# GPIO.net
KiCad netlist of a schematic drawn in Altium Designer
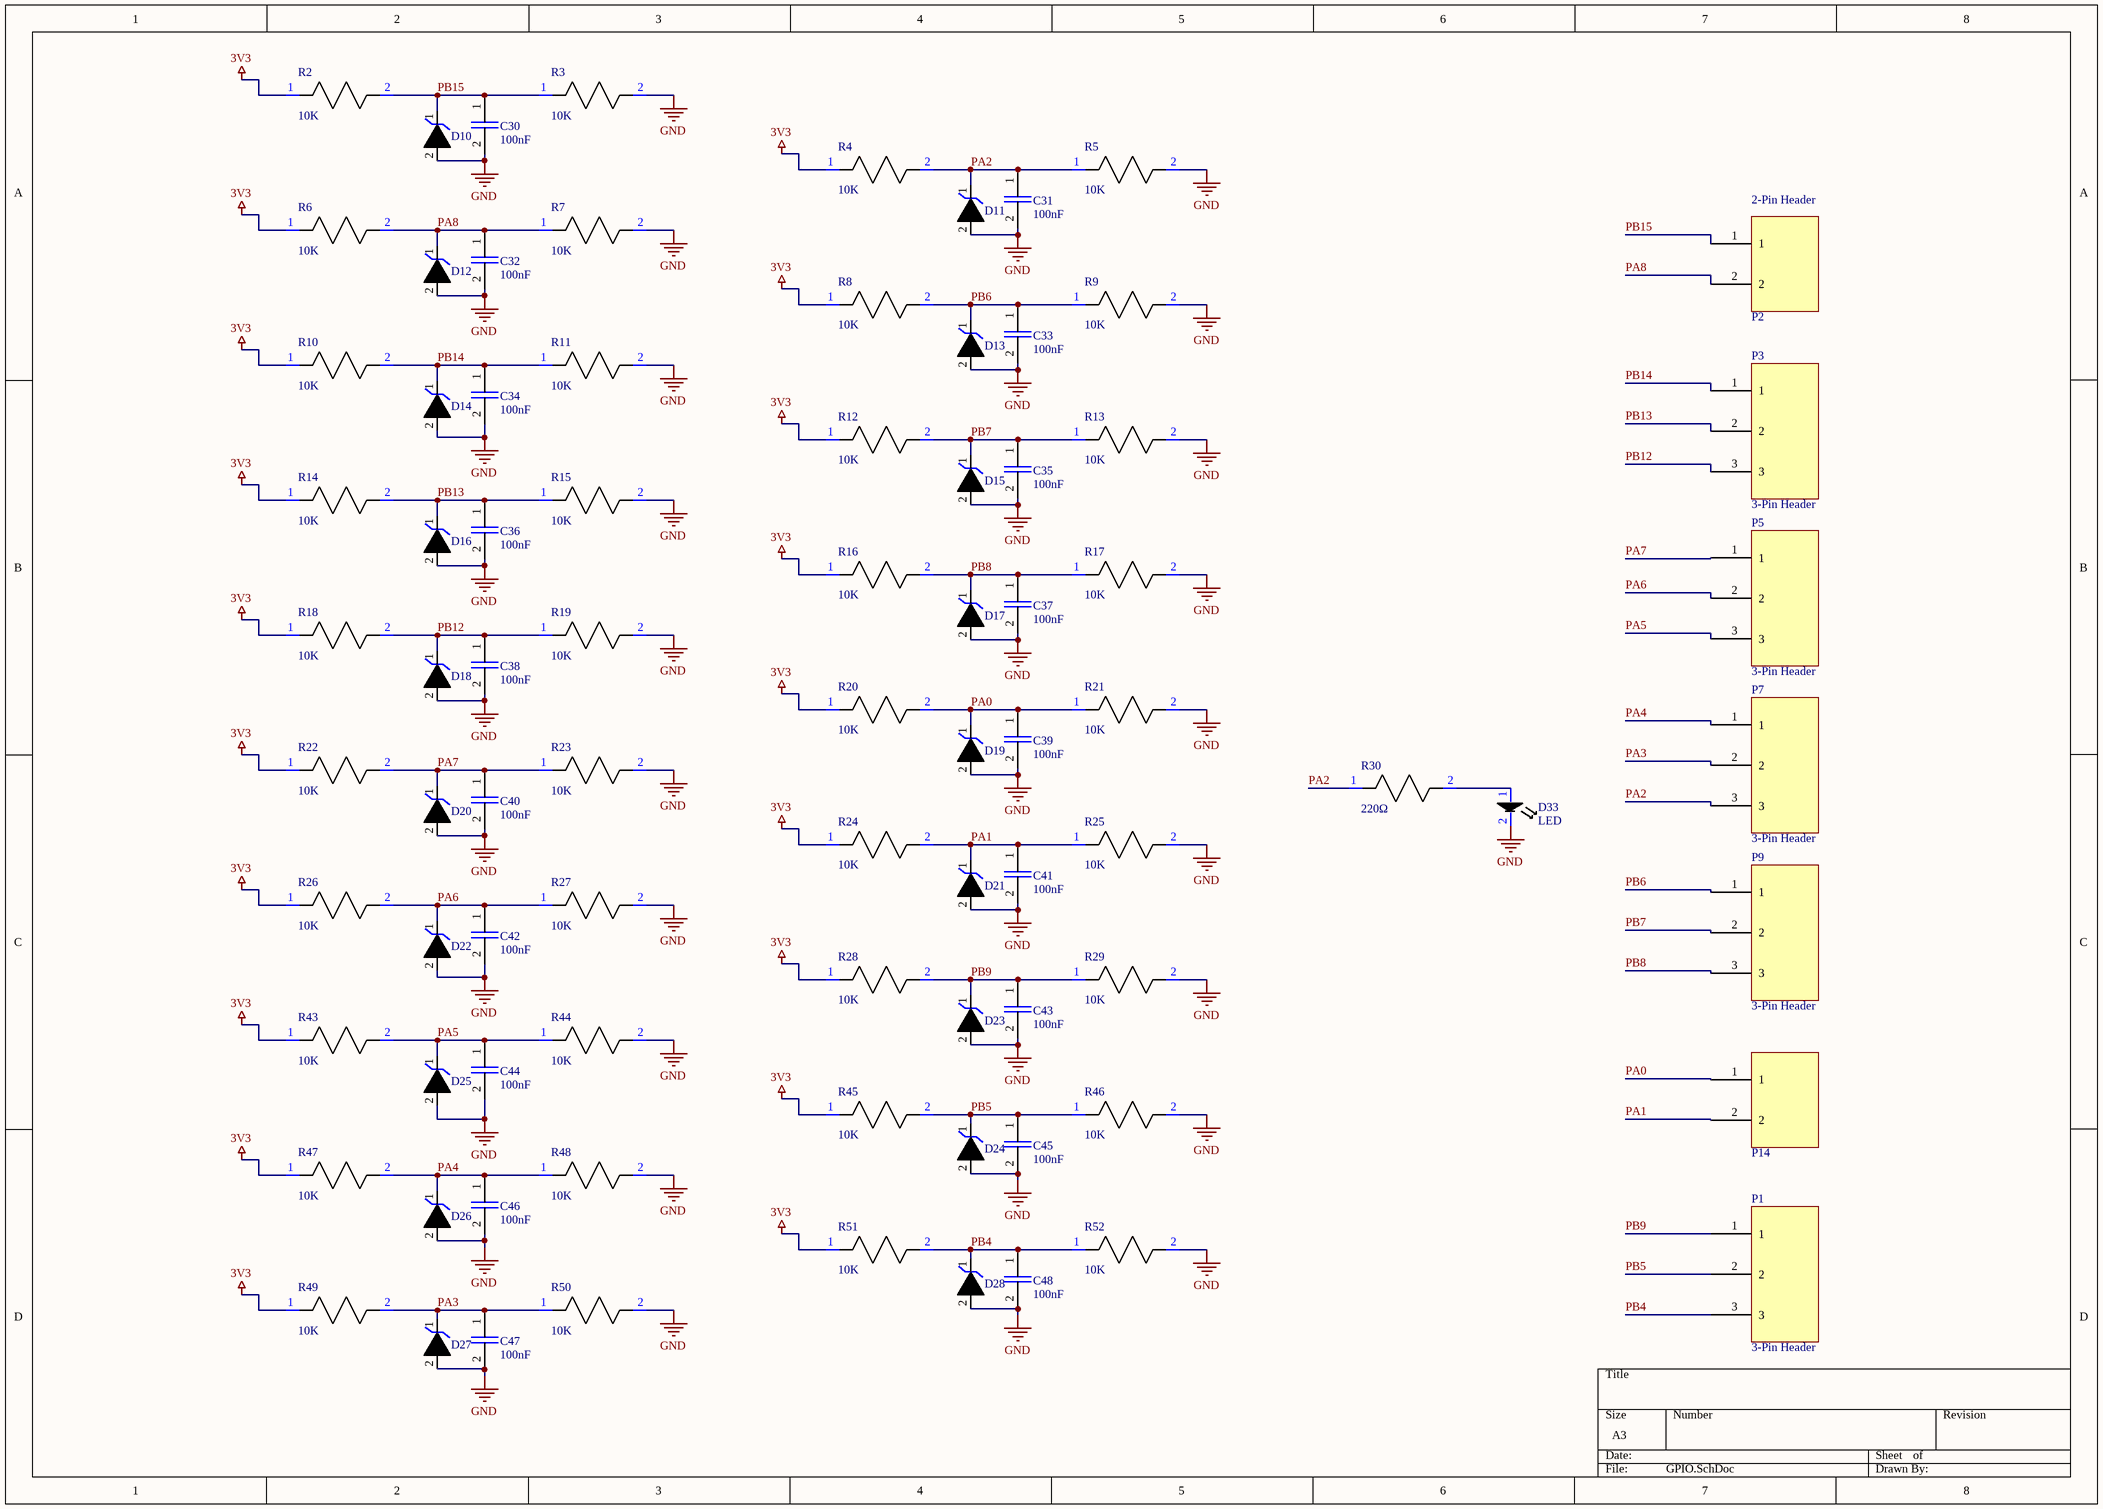
[diagram p0: GPIO.SchDoc]

(export (version "E")
  (design (tool "Eeschema 10.0.6"))
  (components
    (comp (ref "C30")
      (value "100nF")
      (footprint "0603 Cap")
      (description "SMD 0603 (ceramic) capacitor")
      (fields
        (field (name "MANUFACTURER") "Murata")
        (field (name "MANUFACTURER PART NUMBER") "GRM21BR71C225KA12L")
      )
      (libsource (lib "Lib") (part "0603 Cap"))
    )
    (comp (ref "C31")
      (value "100nF")
      (footprint "0603 Cap")
      (description "SMD 0603 (ceramic) capacitor")
      (fields
        (field (name "MANUFACTURER") "Murata")
        (field (name "MANUFACTURER PART NUMBER") "GRM21BR71C225KA12L")
      )
      (libsource (lib "Lib") (part "0603 Cap"))
    )
    (comp (ref "C32")
      (value "100nF")
      (footprint "0603 Cap")
      (description "SMD 0603 (ceramic) capacitor")
      (fields
        (field (name "MANUFACTURER") "Murata")
        (field (name "MANUFACTURER PART NUMBER") "GRM21BR71C225KA12L")
      )
      (libsource (lib "Lib") (part "0603 Cap"))
    )
    (comp (ref "C33")
      (value "100nF")
      (footprint "0603 Cap")
      (description "SMD 0603 (ceramic) capacitor")
      (fields
        (field (name "MANUFACTURER") "Murata")
        (field (name "MANUFACTURER PART NUMBER") "GRM21BR71C225KA12L")
      )
      (libsource (lib "Lib") (part "0603 Cap"))
    )
    (comp (ref "C34")
      (value "100nF")
      (footprint "0603 Cap")
      (description "SMD 0603 (ceramic) capacitor")
      (fields
        (field (name "MANUFACTURER") "Murata")
        (field (name "MANUFACTURER PART NUMBER") "GRM21BR71C225KA12L")
      )
      (libsource (lib "Lib") (part "0603 Cap"))
    )
    (comp (ref "C35")
      (value "100nF")
      (footprint "0603 Cap")
      (description "SMD 0603 (ceramic) capacitor")
      (fields
        (field (name "MANUFACTURER") "Murata")
        (field (name "MANUFACTURER PART NUMBER") "GRM21BR71C225KA12L")
      )
      (libsource (lib "Lib") (part "0603 Cap"))
    )
    (comp (ref "C36")
      (value "100nF")
      (footprint "0603 Cap")
      (description "SMD 0603 (ceramic) capacitor")
      (fields
        (field (name "MANUFACTURER") "Murata")
        (field (name "MANUFACTURER PART NUMBER") "GRM21BR71C225KA12L")
      )
      (libsource (lib "Lib") (part "0603 Cap"))
    )
    (comp (ref "C37")
      (value "100nF")
      (footprint "0603 Cap")
      (description "SMD 0603 (ceramic) capacitor")
      (fields
        (field (name "MANUFACTURER") "Murata")
        (field (name "MANUFACTURER PART NUMBER") "GRM21BR71C225KA12L")
      )
      (libsource (lib "Lib") (part "0603 Cap"))
    )
    (comp (ref "C38")
      (value "100nF")
      (footprint "0603 Cap")
      (description "SMD 0603 (ceramic) capacitor")
      (fields
        (field (name "MANUFACTURER") "Murata")
        (field (name "MANUFACTURER PART NUMBER") "GRM21BR71C225KA12L")
      )
      (libsource (lib "Lib") (part "0603 Cap"))
    )
    (comp (ref "C39")
      (value "100nF")
      (footprint "0603 Cap")
      (description "SMD 0603 (ceramic) capacitor")
      (fields
        (field (name "MANUFACTURER") "Murata")
        (field (name "MANUFACTURER PART NUMBER") "GRM21BR71C225KA12L")
      )
      (libsource (lib "Lib") (part "0603 Cap"))
    )
    (comp (ref "C40")
      (value "100nF")
      (footprint "0603 Cap")
      (description "SMD 0603 (ceramic) capacitor")
      (fields
        (field (name "MANUFACTURER") "Murata")
        (field (name "MANUFACTURER PART NUMBER") "GRM21BR71C225KA12L")
      )
      (libsource (lib "Lib") (part "0603 Cap"))
    )
    (comp (ref "C41")
      (value "100nF")
      (footprint "0603 Cap")
      (description "SMD 0603 (ceramic) capacitor")
      (fields
        (field (name "MANUFACTURER") "Murata")
        (field (name "MANUFACTURER PART NUMBER") "GRM21BR71C225KA12L")
      )
      (libsource (lib "Lib") (part "0603 Cap"))
    )
    (comp (ref "C42")
      (value "100nF")
      (footprint "0603 Cap")
      (description "SMD 0603 (ceramic) capacitor")
      (fields
        (field (name "MANUFACTURER") "Murata")
        (field (name "MANUFACTURER PART NUMBER") "GRM21BR71C225KA12L")
      )
      (libsource (lib "Lib") (part "0603 Cap"))
    )
    (comp (ref "C43")
      (value "100nF")
      (footprint "0603 Cap")
      (description "SMD 0603 (ceramic) capacitor")
      (fields
        (field (name "MANUFACTURER") "Murata")
        (field (name "MANUFACTURER PART NUMBER") "GRM21BR71C225KA12L")
      )
      (libsource (lib "Lib") (part "0603 Cap"))
    )
    (comp (ref "C44")
      (value "100nF")
      (footprint "0603 Cap")
      (description "SMD 0603 (ceramic) capacitor")
      (fields
        (field (name "MANUFACTURER") "Murata")
        (field (name "MANUFACTURER PART NUMBER") "GRM21BR71C225KA12L")
      )
      (libsource (lib "Lib") (part "0603 Cap"))
    )
    (comp (ref "C45")
      (value "100nF")
      (footprint "0603 Cap")
      (description "SMD 0603 (ceramic) capacitor")
      (fields
        (field (name "MANUFACTURER") "Murata")
        (field (name "MANUFACTURER PART NUMBER") "GRM21BR71C225KA12L")
      )
      (libsource (lib "Lib") (part "0603 Cap"))
    )
    (comp (ref "C46")
      (value "100nF")
      (footprint "0603 Cap")
      (description "SMD 0603 (ceramic) capacitor")
      (fields
        (field (name "MANUFACTURER") "Murata")
        (field (name "MANUFACTURER PART NUMBER") "GRM21BR71C225KA12L")
      )
      (libsource (lib "Lib") (part "0603 Cap"))
    )
    (comp (ref "C47")
      (value "100nF")
      (footprint "0603 Cap")
      (description "SMD 0603 (ceramic) capacitor")
      (fields
        (field (name "MANUFACTURER") "Murata")
        (field (name "MANUFACTURER PART NUMBER") "GRM21BR71C225KA12L")
      )
      (libsource (lib "Lib") (part "0603 Cap"))
    )
    (comp (ref "C48")
      (value "100nF")
      (footprint "0603 Cap")
      (description "SMD 0603 (ceramic) capacitor")
      (fields
        (field (name "MANUFACTURER") "Murata")
        (field (name "MANUFACTURER PART NUMBER") "GRM21BR71C225KA12L")
      )
      (libsource (lib "Lib") (part "0603 Cap"))
    )
    (comp (ref "D10")
      (value "TVS")
      (footprint "TVS DIODE")
      (description "Schematic for TVS diode")
      (libsource (lib "Lib") (part "TVS Diode"))
    )
    (comp (ref "D11")
      (value "TVS")
      (footprint "TVS DIODE")
      (description "Schematic for TVS diode")
      (libsource (lib "Lib") (part "TVS Diode"))
    )
    (comp (ref "D12")
      (value "TVS")
      (footprint "TVS DIODE")
      (description "Schematic for TVS diode")
      (libsource (lib "Lib") (part "TVS Diode"))
    )
    (comp (ref "D13")
      (value "TVS")
      (footprint "TVS DIODE")
      (description "Schematic for TVS diode")
      (libsource (lib "Lib") (part "TVS Diode"))
    )
    (comp (ref "D14")
      (value "TVS")
      (footprint "TVS DIODE")
      (description "Schematic for TVS diode")
      (libsource (lib "Lib") (part "TVS Diode"))
    )
    (comp (ref "D15")
      (value "TVS")
      (footprint "TVS DIODE")
      (description "Schematic for TVS diode")
      (libsource (lib "Lib") (part "TVS Diode"))
    )
    (comp (ref "D16")
      (value "TVS")
      (footprint "TVS DIODE")
      (description "Schematic for TVS diode")
      (libsource (lib "Lib") (part "TVS Diode"))
    )
    (comp (ref "D17")
      (value "TVS")
      (footprint "TVS DIODE")
      (description "Schematic for TVS diode")
      (libsource (lib "Lib") (part "TVS Diode"))
    )
    (comp (ref "D18")
      (value "TVS")
      (footprint "TVS DIODE")
      (description "Schematic for TVS diode")
      (libsource (lib "Lib") (part "TVS Diode"))
    )
    (comp (ref "D19")
      (value "TVS")
      (footprint "TVS DIODE")
      (description "Schematic for TVS diode")
      (libsource (lib "Lib") (part "TVS Diode"))
    )
    (comp (ref "D20")
      (value "TVS")
      (footprint "TVS DIODE")
      (description "Schematic for TVS diode")
      (libsource (lib "Lib") (part "TVS Diode"))
    )
    (comp (ref "D21")
      (value "TVS")
      (footprint "TVS DIODE")
      (description "Schematic for TVS diode")
      (libsource (lib "Lib") (part "TVS Diode"))
    )
    (comp (ref "D22")
      (value "TVS")
      (footprint "TVS DIODE")
      (description "Schematic for TVS diode")
      (libsource (lib "Lib") (part "TVS Diode"))
    )
    (comp (ref "D23")
      (value "TVS")
      (footprint "TVS DIODE")
      (description "Schematic for TVS diode")
      (libsource (lib "Lib") (part "TVS Diode"))
    )
    (comp (ref "D24")
      (value "TVS")
      (footprint "TVS DIODE")
      (description "Schematic for TVS diode")
      (libsource (lib "Lib") (part "TVS Diode"))
    )
    (comp (ref "D25")
      (value "TVS")
      (footprint "TVS DIODE")
      (description "Schematic for TVS diode")
      (libsource (lib "Lib") (part "TVS Diode"))
    )
    (comp (ref "D26")
      (value "TVS")
      (footprint "TVS DIODE")
      (description "Schematic for TVS diode")
      (libsource (lib "Lib") (part "TVS Diode"))
    )
    (comp (ref "D27")
      (value "TVS")
      (footprint "TVS DIODE")
      (description "Schematic for TVS diode")
      (libsource (lib "Lib") (part "TVS Diode"))
    )
    (comp (ref "D28")
      (value "TVS")
      (footprint "TVS DIODE")
      (description "Schematic for TVS diode")
      (libsource (lib "Lib") (part "TVS Diode"))
    )
    (comp (ref "D33") (value "LED") (footprint "0805 LED") (libsource (lib "Lib") (part "LED")))
    (comp (ref "P1")
      (value "3-Pin Header")
      (footprint "WR-TBL 322 3H")
      (description "322 Series 3 pin header")
      (libsource (lib "Lib") (part "322-3H"))
    )
    (comp (ref "P2")
      (value "2-Pin Header")
      (footprint "WR-TBL 322 2H")
      (description "322 series 2 pin header")
      (libsource (lib "Lib") (part "322-2H"))
    )
    (comp (ref "P3")
      (value "3-Pin Header")
      (footprint "WR-TBL 322 3H")
      (description "322 Series 3 pin header")
      (libsource (lib "Lib") (part "322-3H"))
    )
    (comp (ref "P5")
      (value "3-Pin Header")
      (footprint "WR-TBL 322 3H")
      (description "322 Series 3 pin header")
      (libsource (lib "Lib") (part "322-3H"))
    )
    (comp (ref "P7")
      (value "3-Pin Header")
      (footprint "WR-TBL 322 3H")
      (description "322 Series 3 pin header")
      (libsource (lib "Lib") (part "322-3H"))
    )
    (comp (ref "P9")
      (value "3-Pin Header")
      (footprint "WR-TBL 322 3H")
      (description "322 Series 3 pin header")
      (libsource (lib "Lib") (part "322-3H"))
    )
    (comp (ref "P14")
      (value "2-Pin Header")
      (footprint "WR-TBL 322 2H")
      (description "322 series 2 pin header")
      (libsource (lib "Lib") (part "322-2H"))
    )
    (comp (ref "R2")
      (value "10K")
      (footprint "0603 RES")
      (description "Can be used for SMD resistors")
      (fields (field (name "Comment") "Resistor"))
      (libsource (lib "Lib") (part "0603 Res"))
    )
    (comp (ref "R3")
      (value "10K")
      (footprint "0603 RES")
      (description "Can be used for SMD resistors")
      (fields (field (name "Comment") "Resistor"))
      (libsource (lib "Lib") (part "0603 Res"))
    )
    (comp (ref "R4")
      (value "10K")
      (footprint "0603 RES")
      (description "Can be used for SMD resistors")
      (fields (field (name "Comment") "Resistor"))
      (libsource (lib "Lib") (part "0603 Res"))
    )
    (comp (ref "R5")
      (value "10K")
      (footprint "0603 RES")
      (description "Can be used for SMD resistors")
      (fields (field (name "Comment") "Resistor"))
      (libsource (lib "Lib") (part "0603 Res"))
    )
    (comp (ref "R6")
      (value "10K")
      (footprint "0603 RES")
      (description "Can be used for SMD resistors")
      (fields (field (name "Comment") "Resistor"))
      (libsource (lib "Lib") (part "0603 Res"))
    )
    (comp (ref "R7")
      (value "10K")
      (footprint "0603 RES")
      (description "Can be used for SMD resistors")
      (fields (field (name "Comment") "Resistor"))
      (libsource (lib "Lib") (part "0603 Res"))
    )
    (comp (ref "R8")
      (value "10K")
      (footprint "0603 RES")
      (description "Can be used for SMD resistors")
      (fields (field (name "Comment") "Resistor"))
      (libsource (lib "Lib") (part "0603 Res"))
    )
    (comp (ref "R9")
      (value "10K")
      (footprint "0603 RES")
      (description "Can be used for SMD resistors")
      (fields (field (name "Comment") "Resistor"))
      (libsource (lib "Lib") (part "0603 Res"))
    )
    (comp (ref "R10")
      (value "10K")
      (footprint "0603 RES")
      (description "Can be used for SMD resistors")
      (fields (field (name "Comment") "Resistor"))
      (libsource (lib "Lib") (part "0603 Res"))
    )
    (comp (ref "R11")
      (value "10K")
      (footprint "0603 RES")
      (description "Can be used for SMD resistors")
      (fields (field (name "Comment") "Resistor"))
      (libsource (lib "Lib") (part "0603 Res"))
    )
    (comp (ref "R12")
      (value "10K")
      (footprint "0603 RES")
      (description "Can be used for SMD resistors")
      (fields (field (name "Comment") "Resistor"))
      (libsource (lib "Lib") (part "0603 Res"))
    )
    (comp (ref "R13")
      (value "10K")
      (footprint "0603 RES")
      (description "Can be used for SMD resistors")
      (fields (field (name "Comment") "Resistor"))
      (libsource (lib "Lib") (part "0603 Res"))
    )
    (comp (ref "R14")
      (value "10K")
      (footprint "0603 RES")
      (description "Can be used for SMD resistors")
      (fields (field (name "Comment") "Resistor"))
      (libsource (lib "Lib") (part "0603 Res"))
    )
    (comp (ref "R15")
      (value "10K")
      (footprint "0603 RES")
      (description "Can be used for SMD resistors")
      (fields (field (name "Comment") "Resistor"))
      (libsource (lib "Lib") (part "0603 Res"))
    )
    (comp (ref "R16")
      (value "10K")
      (footprint "0603 RES")
      (description "Can be used for SMD resistors")
      (fields (field (name "Comment") "Resistor"))
      (libsource (lib "Lib") (part "0603 Res"))
    )
    (comp (ref "R17")
      (value "10K")
      (footprint "0603 RES")
      (description "Can be used for SMD resistors")
      (fields (field (name "Comment") "Resistor"))
      (libsource (lib "Lib") (part "0603 Res"))
    )
    (comp (ref "R18")
      (value "10K")
      (footprint "0603 RES")
      (description "Can be used for SMD resistors")
      (fields (field (name "Comment") "Resistor"))
      (libsource (lib "Lib") (part "0603 Res"))
    )
    (comp (ref "R19")
      (value "10K")
      (footprint "0603 RES")
      (description "Can be used for SMD resistors")
      (fields (field (name "Comment") "Resistor"))
      (libsource (lib "Lib") (part "0603 Res"))
    )
    (comp (ref "R20")
      (value "10K")
      (footprint "0603 RES")
      (description "Can be used for SMD resistors")
      (fields (field (name "Comment") "Resistor"))
      (libsource (lib "Lib") (part "0603 Res"))
    )
    (comp (ref "R21")
      (value "10K")
      (footprint "0603 RES")
      (description "Can be used for SMD resistors")
      (fields (field (name "Comment") "Resistor"))
      (libsource (lib "Lib") (part "0603 Res"))
    )
    (comp (ref "R22")
      (value "10K")
      (footprint "0603 RES")
      (description "Can be used for SMD resistors")
      (fields (field (name "Comment") "Resistor"))
      (libsource (lib "Lib") (part "0603 Res"))
    )
    (comp (ref "R23")
      (value "10K")
      (footprint "0603 RES")
      (description "Can be used for SMD resistors")
      (fields (field (name "Comment") "Resistor"))
      (libsource (lib "Lib") (part "0603 Res"))
    )
    (comp (ref "R24")
      (value "10K")
      (footprint "0603 RES")
      (description "Can be used for SMD resistors")
      (fields (field (name "Comment") "Resistor"))
      (libsource (lib "Lib") (part "0603 Res"))
    )
    (comp (ref "R25")
      (value "10K")
      (footprint "0603 RES")
      (description "Can be used for SMD resistors")
      (fields (field (name "Comment") "Resistor"))
      (libsource (lib "Lib") (part "0603 Res"))
    )
    (comp (ref "R26")
      (value "10K")
      (footprint "0603 RES")
      (description "Can be used for SMD resistors")
      (fields (field (name "Comment") "Resistor"))
      (libsource (lib "Lib") (part "0603 Res"))
    )
    (comp (ref "R27")
      (value "10K")
      (footprint "0603 RES")
      (description "Can be used for SMD resistors")
      (fields (field (name "Comment") "Resistor"))
      (libsource (lib "Lib") (part "0603 Res"))
    )
    (comp (ref "R28")
      (value "10K")
      (footprint "0603 RES")
      (description "Can be used for SMD resistors")
      (fields (field (name "Comment") "Resistor"))
      (libsource (lib "Lib") (part "0603 Res"))
    )
    (comp (ref "R29")
      (value "10K")
      (footprint "0603 RES")
      (description "Can be used for SMD resistors")
      (fields (field (name "Comment") "Resistor"))
      (libsource (lib "Lib") (part "0603 Res"))
    )
    (comp (ref "R30")
      (value "220Ω")
      (footprint "0603 RES")
      (description "Can be used for SMD resistors")
      (fields (field (name "Comment") "Resistor"))
      (libsource (lib "Lib") (part "0603 Res"))
    )
    (comp (ref "R43")
      (value "10K")
      (footprint "0603 RES")
      (description "Can be used for SMD resistors")
      (fields (field (name "Comment") "Resistor"))
      (libsource (lib "Lib") (part "0603 Res"))
    )
    (comp (ref "R44")
      (value "10K")
      (footprint "0603 RES")
      (description "Can be used for SMD resistors")
      (fields (field (name "Comment") "Resistor"))
      (libsource (lib "Lib") (part "0603 Res"))
    )
    (comp (ref "R45")
      (value "10K")
      (footprint "0603 RES")
      (description "Can be used for SMD resistors")
      (fields (field (name "Comment") "Resistor"))
      (libsource (lib "Lib") (part "0603 Res"))
    )
    (comp (ref "R46")
      (value "10K")
      (footprint "0603 RES")
      (description "Can be used for SMD resistors")
      (fields (field (name "Comment") "Resistor"))
      (libsource (lib "Lib") (part "0603 Res"))
    )
    (comp (ref "R47")
      (value "10K")
      (footprint "0603 RES")
      (description "Can be used for SMD resistors")
      (fields (field (name "Comment") "Resistor"))
      (libsource (lib "Lib") (part "0603 Res"))
    )
    (comp (ref "R48")
      (value "10K")
      (footprint "0603 RES")
      (description "Can be used for SMD resistors")
      (fields (field (name "Comment") "Resistor"))
      (libsource (lib "Lib") (part "0603 Res"))
    )
    (comp (ref "R49")
      (value "10K")
      (footprint "0603 RES")
      (description "Can be used for SMD resistors")
      (fields (field (name "Comment") "Resistor"))
      (libsource (lib "Lib") (part "0603 Res"))
    )
    (comp (ref "R50")
      (value "10K")
      (footprint "0603 RES")
      (description "Can be used for SMD resistors")
      (fields (field (name "Comment") "Resistor"))
      (libsource (lib "Lib") (part "0603 Res"))
    )
    (comp (ref "R51")
      (value "10K")
      (footprint "0603 RES")
      (description "Can be used for SMD resistors")
      (fields (field (name "Comment") "Resistor"))
      (libsource (lib "Lib") (part "0603 Res"))
    )
    (comp (ref "R52")
      (value "10K")
      (footprint "0603 RES")
      (description "Can be used for SMD resistors")
      (fields (field (name "Comment") "Resistor"))
      (libsource (lib "Lib") (part "0603 Res"))
    )
  )
  (nets
    (net (code "1") (name "/PA0") (class "Default")
      (node (ref "C39") (pin "1") (pinfunction "11_1") (pintype "passive"))
      (node (ref "D19") (pin "1") (pinfunction "1_1") (pintype "passive"))
      (node (ref "P14") (pin "1") (pinfunction "1_1") (pintype "passive"))
      (node (ref "R20") (pin "2") (pinfunction "21_2") (pintype "passive"))
      (node (ref "R21") (pin "1") (pinfunction "22_1") (pintype "passive"))
    )
    (net (code "2") (name "/PA1") (class "Default")
      (node (ref "C41") (pin "1") (pinfunction "11_1") (pintype "passive"))
      (node (ref "D21") (pin "1") (pinfunction "1_1") (pintype "passive"))
      (node (ref "P14") (pin "2") (pinfunction "2_2") (pintype "passive"))
      (node (ref "R24") (pin "2") (pinfunction "21_2") (pintype "passive"))
      (node (ref "R25") (pin "1") (pinfunction "22_1") (pintype "passive"))
    )
    (net (code "3") (name "/PA2") (class "Default")
      (node (ref "C31") (pin "1") (pinfunction "11_1") (pintype "passive"))
      (node (ref "D11") (pin "1") (pinfunction "1_1") (pintype "passive"))
      (node (ref "P7") (pin "3") (pinfunction "3_3") (pintype "passive"))
      (node (ref "R30") (pin "1") (pinfunction "22_1") (pintype "passive"))
      (node (ref "R4") (pin "2") (pinfunction "21_2") (pintype "passive"))
      (node (ref "R5") (pin "1") (pinfunction "22_1") (pintype "passive"))
    )
    (net (code "4") (name "/PA3") (class "Default")
      (node (ref "C47") (pin "1") (pinfunction "11_1") (pintype "passive"))
      (node (ref "D27") (pin "1") (pinfunction "1_1") (pintype "passive"))
      (node (ref "P7") (pin "2") (pinfunction "2_2") (pintype "passive"))
      (node (ref "R49") (pin "2") (pinfunction "21_2") (pintype "passive"))
      (node (ref "R50") (pin "1") (pinfunction "22_1") (pintype "passive"))
    )
    (net (code "5") (name "/PA4") (class "Default")
      (node (ref "C46") (pin "1") (pinfunction "11_1") (pintype "passive"))
      (node (ref "D26") (pin "1") (pinfunction "1_1") (pintype "passive"))
      (node (ref "P7") (pin "1") (pinfunction "1_1") (pintype "passive"))
      (node (ref "R47") (pin "2") (pinfunction "21_2") (pintype "passive"))
      (node (ref "R48") (pin "1") (pinfunction "22_1") (pintype "passive"))
    )
    (net (code "6") (name "/PA5") (class "Default")
      (node (ref "C44") (pin "1") (pinfunction "11_1") (pintype "passive"))
      (node (ref "D25") (pin "1") (pinfunction "1_1") (pintype "passive"))
      (node (ref "P5") (pin "3") (pinfunction "3_3") (pintype "passive"))
      (node (ref "R43") (pin "2") (pinfunction "21_2") (pintype "passive"))
      (node (ref "R44") (pin "1") (pinfunction "22_1") (pintype "passive"))
    )
    (net (code "7") (name "/PA6") (class "Default")
      (node (ref "C42") (pin "1") (pinfunction "11_1") (pintype "passive"))
      (node (ref "D22") (pin "1") (pinfunction "1_1") (pintype "passive"))
      (node (ref "P5") (pin "2") (pinfunction "2_2") (pintype "passive"))
      (node (ref "R26") (pin "2") (pinfunction "21_2") (pintype "passive"))
      (node (ref "R27") (pin "1") (pinfunction "22_1") (pintype "passive"))
    )
    (net (code "8") (name "/PA7") (class "Default")
      (node (ref "C40") (pin "1") (pinfunction "11_1") (pintype "passive"))
      (node (ref "D20") (pin "1") (pinfunction "1_1") (pintype "passive"))
      (node (ref "P5") (pin "1") (pinfunction "1_1") (pintype "passive"))
      (node (ref "R22") (pin "2") (pinfunction "21_2") (pintype "passive"))
      (node (ref "R23") (pin "1") (pinfunction "22_1") (pintype "passive"))
    )
    (net (code "9") (name "/PA8") (class "Default")
      (node (ref "C32") (pin "1") (pinfunction "11_1") (pintype "passive"))
      (node (ref "D12") (pin "1") (pinfunction "1_1") (pintype "passive"))
      (node (ref "P2") (pin "2") (pinfunction "2_2") (pintype "passive"))
      (node (ref "R6") (pin "2") (pinfunction "21_2") (pintype "passive"))
      (node (ref "R7") (pin "1") (pinfunction "22_1") (pintype "passive"))
    )
    (net (code "10") (name "/PB4") (class "Default")
      (node (ref "C48") (pin "1") (pinfunction "11_1") (pintype "passive"))
      (node (ref "D28") (pin "1") (pinfunction "1_1") (pintype "passive"))
      (node (ref "P1") (pin "3") (pinfunction "3_3") (pintype "passive"))
      (node (ref "R51") (pin "2") (pinfunction "21_2") (pintype "passive"))
      (node (ref "R52") (pin "1") (pinfunction "22_1") (pintype "passive"))
    )
    (net (code "11") (name "/PB5") (class "Default")
      (node (ref "C45") (pin "1") (pinfunction "11_1") (pintype "passive"))
      (node (ref "D24") (pin "1") (pinfunction "1_1") (pintype "passive"))
      (node (ref "P1") (pin "2") (pinfunction "2_2") (pintype "passive"))
      (node (ref "R45") (pin "2") (pinfunction "21_2") (pintype "passive"))
      (node (ref "R46") (pin "1") (pinfunction "22_1") (pintype "passive"))
    )
    (net (code "12") (name "/PB6") (class "Default")
      (node (ref "C33") (pin "1") (pinfunction "11_1") (pintype "passive"))
      (node (ref "D13") (pin "1") (pinfunction "1_1") (pintype "passive"))
      (node (ref "P9") (pin "1") (pinfunction "1_1") (pintype "passive"))
      (node (ref "R8") (pin "2") (pinfunction "21_2") (pintype "passive"))
      (node (ref "R9") (pin "1") (pinfunction "22_1") (pintype "passive"))
    )
    (net (code "13") (name "/PB7") (class "Default")
      (node (ref "C35") (pin "1") (pinfunction "11_1") (pintype "passive"))
      (node (ref "D15") (pin "1") (pinfunction "1_1") (pintype "passive"))
      (node (ref "P9") (pin "2") (pinfunction "2_2") (pintype "passive"))
      (node (ref "R12") (pin "2") (pinfunction "21_2") (pintype "passive"))
      (node (ref "R13") (pin "1") (pinfunction "22_1") (pintype "passive"))
    )
    (net (code "14") (name "/PB8") (class "Default")
      (node (ref "C37") (pin "1") (pinfunction "11_1") (pintype "passive"))
      (node (ref "D17") (pin "1") (pinfunction "1_1") (pintype "passive"))
      (node (ref "P9") (pin "3") (pinfunction "3_3") (pintype "passive"))
      (node (ref "R16") (pin "2") (pinfunction "21_2") (pintype "passive"))
      (node (ref "R17") (pin "1") (pinfunction "22_1") (pintype "passive"))
    )
    (net (code "15") (name "/PB9") (class "Default")
      (node (ref "C43") (pin "1") (pinfunction "11_1") (pintype "passive"))
      (node (ref "D23") (pin "1") (pinfunction "1_1") (pintype "passive"))
      (node (ref "P1") (pin "1") (pinfunction "1_1") (pintype "passive"))
      (node (ref "R28") (pin "2") (pinfunction "21_2") (pintype "passive"))
      (node (ref "R29") (pin "1") (pinfunction "22_1") (pintype "passive"))
    )
    (net (code "16") (name "/PB12") (class "Default")
      (node (ref "C38") (pin "1") (pinfunction "11_1") (pintype "passive"))
      (node (ref "D18") (pin "1") (pinfunction "1_1") (pintype "passive"))
      (node (ref "P3") (pin "3") (pinfunction "3_3") (pintype "passive"))
      (node (ref "R18") (pin "2") (pinfunction "21_2") (pintype "passive"))
      (node (ref "R19") (pin "1") (pinfunction "22_1") (pintype "passive"))
    )
    (net (code "17") (name "/PB13") (class "Default")
      (node (ref "C36") (pin "1") (pinfunction "11_1") (pintype "passive"))
      (node (ref "D16") (pin "1") (pinfunction "1_1") (pintype "passive"))
      (node (ref "P3") (pin "2") (pinfunction "2_2") (pintype "passive"))
      (node (ref "R14") (pin "2") (pinfunction "21_2") (pintype "passive"))
      (node (ref "R15") (pin "1") (pinfunction "22_1") (pintype "passive"))
    )
    (net (code "18") (name "/PB14") (class "Default")
      (node (ref "C34") (pin "1") (pinfunction "11_1") (pintype "passive"))
      (node (ref "D14") (pin "1") (pinfunction "1_1") (pintype "passive"))
      (node (ref "P3") (pin "1") (pinfunction "1_1") (pintype "passive"))
      (node (ref "R10") (pin "2") (pinfunction "21_2") (pintype "passive"))
      (node (ref "R11") (pin "1") (pinfunction "22_1") (pintype "passive"))
    )
    (net (code "19") (name "/PB15") (class "Default")
      (node (ref "C30") (pin "1") (pinfunction "11_1") (pintype "passive"))
      (node (ref "D10") (pin "1") (pinfunction "1_1") (pintype "passive"))
      (node (ref "P2") (pin "1") (pinfunction "1_1") (pintype "passive"))
      (node (ref "R2") (pin "2") (pinfunction "21_2") (pintype "passive"))
      (node (ref "R3") (pin "1") (pinfunction "22_1") (pintype "passive"))
    )
    (net (code "20") (name "3V3") (class "Default")
      (node (ref "R10") (pin "1") (pinfunction "22_1") (pintype "passive"))
      (node (ref "R12") (pin "1") (pinfunction "22_1") (pintype "passive"))
      (node (ref "R14") (pin "1") (pinfunction "22_1") (pintype "passive"))
      (node (ref "R16") (pin "1") (pinfunction "22_1") (pintype "passive"))
      (node (ref "R18") (pin "1") (pinfunction "22_1") (pintype "passive"))
      (node (ref "R2") (pin "1") (pinfunction "22_1") (pintype "passive"))
      (node (ref "R20") (pin "1") (pinfunction "22_1") (pintype "passive"))
      (node (ref "R22") (pin "1") (pinfunction "22_1") (pintype "passive"))
      (node (ref "R24") (pin "1") (pinfunction "22_1") (pintype "passive"))
      (node (ref "R26") (pin "1") (pinfunction "22_1") (pintype "passive"))
      (node (ref "R28") (pin "1") (pinfunction "22_1") (pintype "passive"))
      (node (ref "R4") (pin "1") (pinfunction "22_1") (pintype "passive"))
      (node (ref "R43") (pin "1") (pinfunction "22_1") (pintype "passive"))
      (node (ref "R45") (pin "1") (pinfunction "22_1") (pintype "passive"))
      (node (ref "R47") (pin "1") (pinfunction "22_1") (pintype "passive"))
      (node (ref "R49") (pin "1") (pinfunction "22_1") (pintype "passive"))
      (node (ref "R51") (pin "1") (pinfunction "22_1") (pintype "passive"))
      (node (ref "R6") (pin "1") (pinfunction "22_1") (pintype "passive"))
      (node (ref "R8") (pin "1") (pinfunction "22_1") (pintype "passive"))
    )
    (net (code "21") (name "GND") (class "Default")
      (node (ref "C30") (pin "2") (pinfunction "12_2") (pintype "passive"))
      (node (ref "C31") (pin "2") (pinfunction "12_2") (pintype "passive"))
      (node (ref "C32") (pin "2") (pinfunction "12_2") (pintype "passive"))
      (node (ref "C33") (pin "2") (pinfunction "12_2") (pintype "passive"))
      (node (ref "C34") (pin "2") (pinfunction "12_2") (pintype "passive"))
      (node (ref "C35") (pin "2") (pinfunction "12_2") (pintype "passive"))
      (node (ref "C36") (pin "2") (pinfunction "12_2") (pintype "passive"))
      (node (ref "C37") (pin "2") (pinfunction "12_2") (pintype "passive"))
      (node (ref "C38") (pin "2") (pinfunction "12_2") (pintype "passive"))
      (node (ref "C39") (pin "2") (pinfunction "12_2") (pintype "passive"))
      (node (ref "C40") (pin "2") (pinfunction "12_2") (pintype "passive"))
      (node (ref "C41") (pin "2") (pinfunction "12_2") (pintype "passive"))
      (node (ref "C42") (pin "2") (pinfunction "12_2") (pintype "passive"))
      (node (ref "C43") (pin "2") (pinfunction "12_2") (pintype "passive"))
      (node (ref "C44") (pin "2") (pinfunction "12_2") (pintype "passive"))
      (node (ref "C45") (pin "2") (pinfunction "12_2") (pintype "passive"))
      (node (ref "C46") (pin "2") (pinfunction "12_2") (pintype "passive"))
      (node (ref "C47") (pin "2") (pinfunction "12_2") (pintype "passive"))
      (node (ref "C48") (pin "2") (pinfunction "12_2") (pintype "passive"))
      (node (ref "D10") (pin "2") (pinfunction "2_2") (pintype "passive"))
      (node (ref "D11") (pin "2") (pinfunction "2_2") (pintype "passive"))
      (node (ref "D12") (pin "2") (pinfunction "2_2") (pintype "passive"))
      (node (ref "D13") (pin "2") (pinfunction "2_2") (pintype "passive"))
      (node (ref "D14") (pin "2") (pinfunction "2_2") (pintype "passive"))
      (node (ref "D15") (pin "2") (pinfunction "2_2") (pintype "passive"))
      (node (ref "D16") (pin "2") (pinfunction "2_2") (pintype "passive"))
      (node (ref "D17") (pin "2") (pinfunction "2_2") (pintype "passive"))
      (node (ref "D18") (pin "2") (pinfunction "2_2") (pintype "passive"))
      (node (ref "D19") (pin "2") (pinfunction "2_2") (pintype "passive"))
      (node (ref "D20") (pin "2") (pinfunction "2_2") (pintype "passive"))
      (node (ref "D21") (pin "2") (pinfunction "2_2") (pintype "passive"))
      (node (ref "D22") (pin "2") (pinfunction "2_2") (pintype "passive"))
      (node (ref "D23") (pin "2") (pinfunction "2_2") (pintype "passive"))
      (node (ref "D24") (pin "2") (pinfunction "2_2") (pintype "passive"))
      (node (ref "D25") (pin "2") (pinfunction "2_2") (pintype "passive"))
      (node (ref "D26") (pin "2") (pinfunction "2_2") (pintype "passive"))
      (node (ref "D27") (pin "2") (pinfunction "2_2") (pintype "passive"))
      (node (ref "D28") (pin "2") (pinfunction "2_2") (pintype "passive"))
      (node (ref "D33") (pin "2") (pinfunction "2_2") (pintype "passive"))
      (node (ref "R11") (pin "2") (pinfunction "21_2") (pintype "passive"))
      (node (ref "R13") (pin "2") (pinfunction "21_2") (pintype "passive"))
      (node (ref "R15") (pin "2") (pinfunction "21_2") (pintype "passive"))
      (node (ref "R17") (pin "2") (pinfunction "21_2") (pintype "passive"))
      (node (ref "R19") (pin "2") (pinfunction "21_2") (pintype "passive"))
      (node (ref "R21") (pin "2") (pinfunction "21_2") (pintype "passive"))
      (node (ref "R23") (pin "2") (pinfunction "21_2") (pintype "passive"))
      (node (ref "R25") (pin "2") (pinfunction "21_2") (pintype "passive"))
      (node (ref "R27") (pin "2") (pinfunction "21_2") (pintype "passive"))
      (node (ref "R29") (pin "2") (pinfunction "21_2") (pintype "passive"))
      (node (ref "R3") (pin "2") (pinfunction "21_2") (pintype "passive"))
      (node (ref "R44") (pin "2") (pinfunction "21_2") (pintype "passive"))
      (node (ref "R46") (pin "2") (pinfunction "21_2") (pintype "passive"))
      (node (ref "R48") (pin "2") (pinfunction "21_2") (pintype "passive"))
      (node (ref "R5") (pin "2") (pinfunction "21_2") (pintype "passive"))
      (node (ref "R50") (pin "2") (pinfunction "21_2") (pintype "passive"))
      (node (ref "R52") (pin "2") (pinfunction "21_2") (pintype "passive"))
      (node (ref "R7") (pin "2") (pinfunction "21_2") (pintype "passive"))
      (node (ref "R9") (pin "2") (pinfunction "21_2") (pintype "passive"))
    )
    (net (code "22") (name "Net-(R30-21)") (class "Default")
      (node (ref "D33") (pin "1") (pinfunction "1_1") (pintype "passive"))
      (node (ref "R30") (pin "2") (pinfunction "21_2") (pintype "passive"))
    )
  )
)
